# gcgc2.net
KiCad netlist of a schematic drawn in EasyEDA
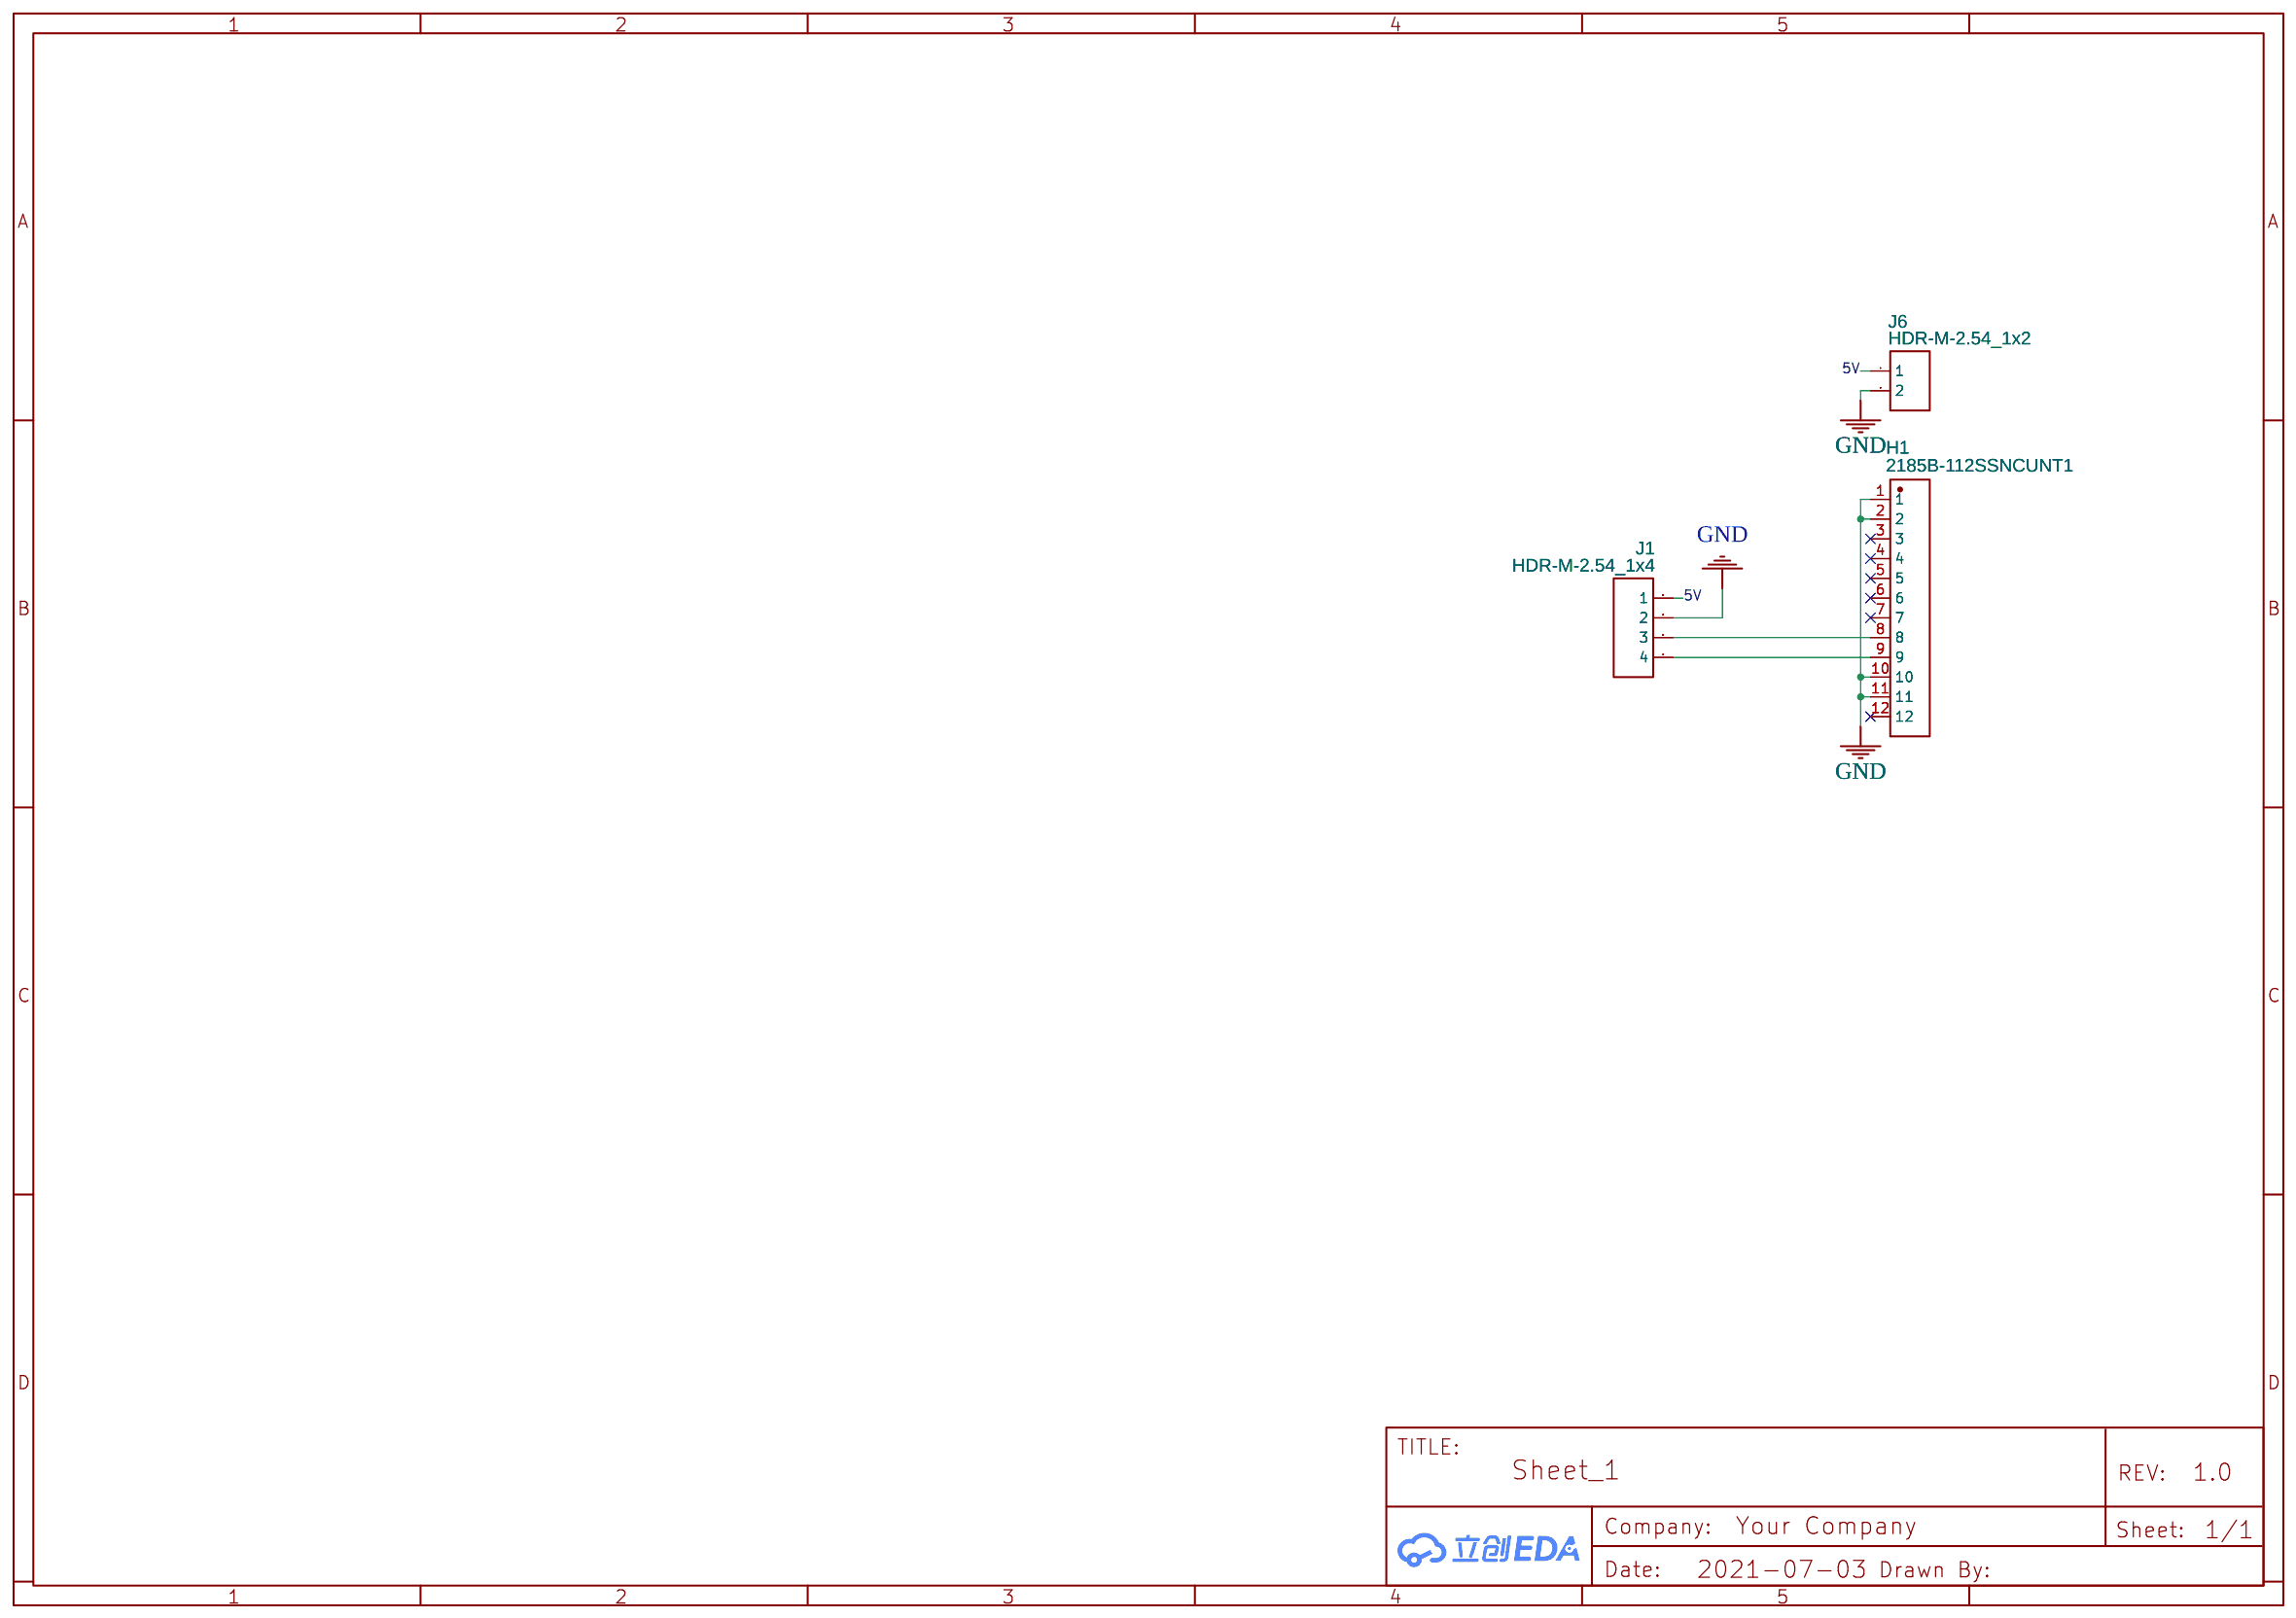
[diagram p0: schematic sheet]

(export (version "E")
  (design (tool "Eeschema 10.0.6"))
  (components
    (comp (ref "H1")
      (value "2185B-112SSNCUNT1")
      (fields (field (name "BOM_Supplier Part") "C721800"))
      (libsource (lib "") (part "2185B-112SSNCUNT1"))
    )
    (comp (ref "J1")
      (value "HDR-M-2.54_1x4")
      (fields (field (name "BOM_Supplier Part") "C124378"))
      (libsource (lib "") (part "HDR-M-2.54_1x4"))
    )
    (comp (ref "J6")
      (value "HDR-M-2.54_1x2")
      (fields (field (name "BOM_Supplier Part") "C124375"))
      (libsource (lib "") (part "HDR-M-2.54_1x2"))
    )
  )
  (nets
    (net (code "1") (name "/5V") (class "Default")
      (node (ref "J1") (pin "1") (pinfunction "1_1") (pintype "unspecified"))
      (node (ref "J6") (pin "1") (pinfunction "1_1") (pintype "unspecified"))
    )
    (net (code "2") (name "GND") (class "Default")
      (node (ref "H1") (pin "1") (pinfunction "1_1") (pintype "unspecified"))
      (node (ref "H1") (pin "10") (pinfunction "10_10") (pintype "unspecified"))
      (node (ref "H1") (pin "11") (pinfunction "11_11") (pintype "unspecified"))
      (node (ref "H1") (pin "2") (pinfunction "2_2") (pintype "unspecified"))
      (node (ref "J1") (pin "2") (pinfunction "2_2") (pintype "unspecified"))
      (node (ref "J6") (pin "2") (pinfunction "2_2") (pintype "unspecified"))
    )
    (net (code "3") (name "Net-(H1-Pad8)") (class "Default")
      (node (ref "H1") (pin "8") (pinfunction "8_8") (pintype "unspecified"))
      (node (ref "J1") (pin "3") (pinfunction "3_3") (pintype "unspecified"))
    )
    (net (code "4") (name "Net-(H1-Pad9)") (class "Default")
      (node (ref "H1") (pin "9") (pinfunction "9_9") (pintype "unspecified"))
      (node (ref "J1") (pin "4") (pinfunction "4_4") (pintype "unspecified"))
    )
    (net (code "5") (name "unconnected-(H1-Pad3)") (class "Default")
      (node (ref "H1") (pin "3") (pinfunction "3_3") (pintype "unspecified+no_connect"))
    )
    (net (code "6") (name "unconnected-(H1-Pad4)") (class "Default")
      (node (ref "H1") (pin "4") (pinfunction "4_4") (pintype "unspecified+no_connect"))
    )
    (net (code "7") (name "unconnected-(H1-Pad5)") (class "Default")
      (node (ref "H1") (pin "5") (pinfunction "5_5") (pintype "unspecified+no_connect"))
    )
    (net (code "8") (name "unconnected-(H1-Pad6)") (class "Default")
      (node (ref "H1") (pin "6") (pinfunction "6_6") (pintype "unspecified+no_connect"))
    )
    (net (code "9") (name "unconnected-(H1-Pad7)") (class "Default")
      (node (ref "H1") (pin "7") (pinfunction "7_7") (pintype "unspecified+no_connect"))
    )
    (net (code "10") (name "unconnected-(H1-Pad12)") (class "Default")
      (node (ref "H1") (pin "12") (pinfunction "12_12") (pintype "unspecified+no_connect"))
    )
  )
)
